# ABC_Maker_V1.net
KiCad netlist of a schematic drawn in Altium Designer
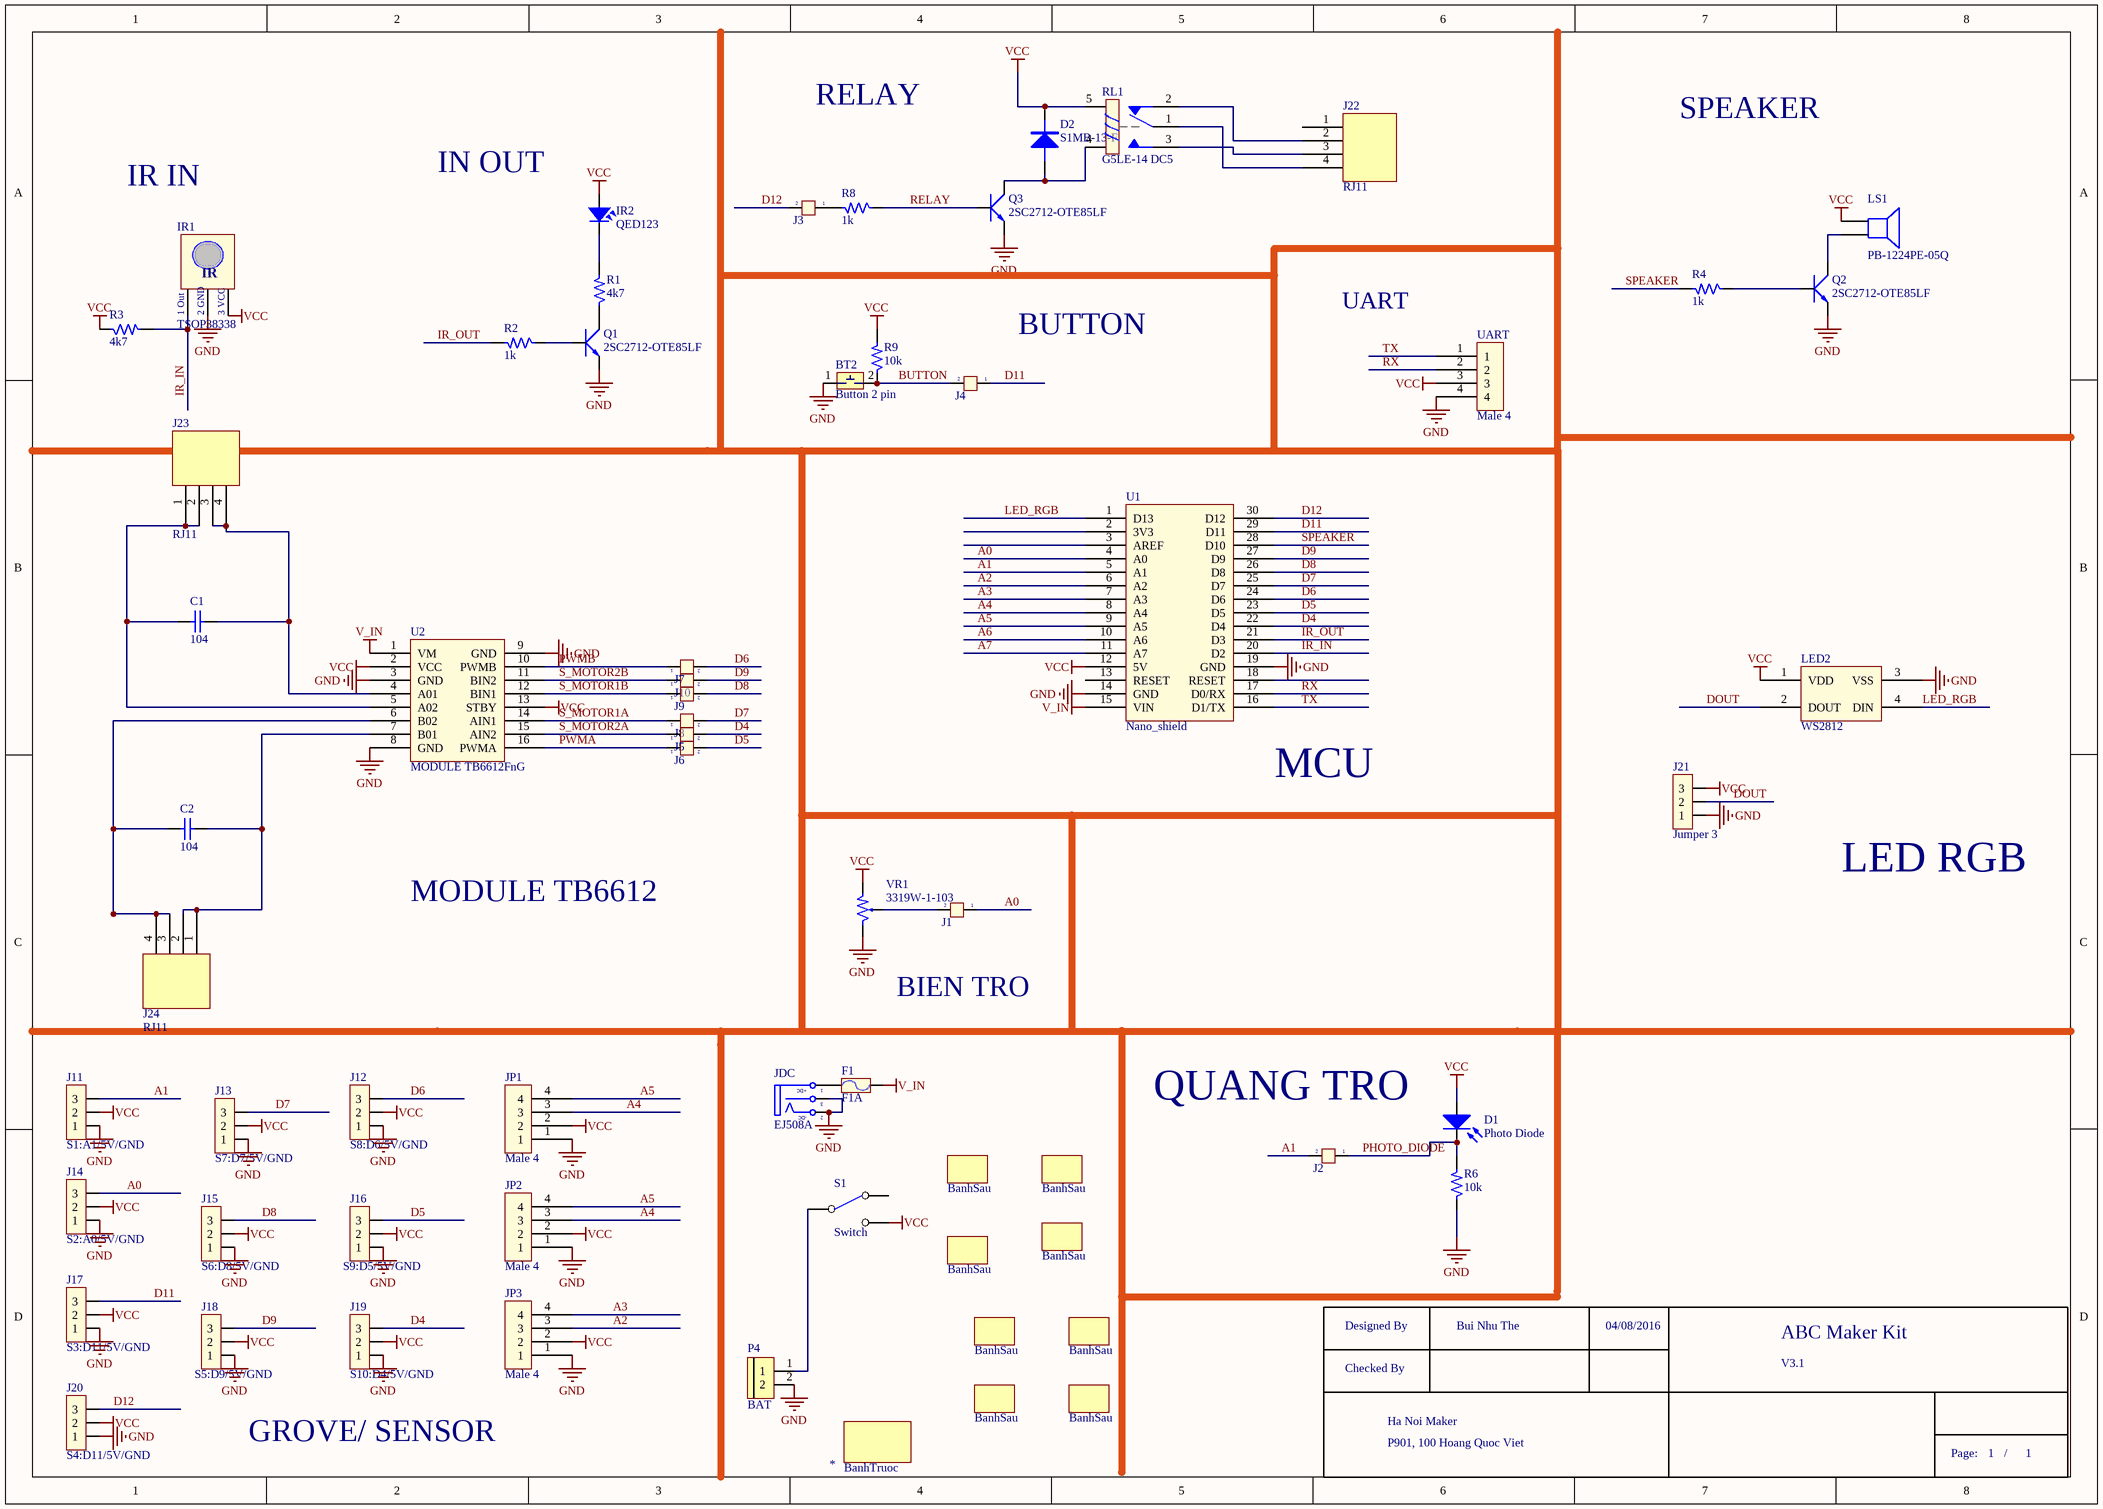
[diagram p0: ABC Maker V1.SchDoc]

(export (version "E")
  (design (tool "Eeschema 10.0.6"))
  (components
    (comp (ref "BT2") (value "Button 2 pin") (libsource (lib "switches") (part "Button 2 pin")))
    (comp (ref "C1") (value "104") (footprint "0805") (libsource (lib "BNTLIB") (part "Cap")))
    (comp (ref "C2") (value "104") (footprint "0805") (libsource (lib "BNTLIB") (part "Cap")))
    (comp (ref "D1")
      (value "Photo Diode")
      (footprint "LED-5 GRe")
      (description "Photosensitive Diode")
      (libsource (lib "BNTLIB") (part "Photo Diode"))
    )
    (comp (ref "D2")
      (value "S1MB-13-F")
      (description "Diode Standard 1000V (1kV) 1A Surface Mount SMB")
      (fields (field (name "MANUFACTURER") "Diodes Incorporated"))
      (libsource (lib "Diode") (part "S1MB-13-F"))
    )
    (comp (ref "F1")
      (value "F1A")
      (footprint "1206")
      (description "Fuse")
      (fields (field (name "DESIGNED BY") "VanDungEvn"))
      (libsource (lib "syhaunguyen") (part "Fuse"))
    )
    (comp (ref "IR1")
      (value "TSOP38338")
      (description "IC IR RCVR MOD 38KHZ DOME RADIAL")
      (fields (field (name "MANUFACTURER") "Vishay Semiconductor Opto Division"))
      (libsource (lib "Sensor") (part "TSOP38338"))
    )
    (comp (ref "IR2")
      (value "QED123")
      (description "Infrared Emitters 80mW/sr 1.7V IR LED")
      (fields (field (name "MANUFACTURER") "Fairchild Semiconductor"))
      (libsource (lib "Sensor") (part "QED123"))
    )
    (comp (ref "J1") (value "Jumper 2") (footprint "JP 2") (libsource (lib "BNTLIB") (part "JP 2")))
    (comp (ref "J2") (value "Jumper 2") (footprint "JP 2") (libsource (lib "BNTLIB") (part "JP 2")))
    (comp (ref "J3") (value "Jumper 2") (footprint "JP 2") (libsource (lib "BNTLIB") (part "JP 2")))
    (comp (ref "J4") (value "Jumper 2") (footprint "JP 2") (libsource (lib "BNTLIB") (part "JP 2")))
    (comp (ref "J5") (value "Jumper 2") (footprint "JP 2") (libsource (lib "") (part "JP 2_1")))
    (comp (ref "J6") (value "Jumper 2") (footprint "JP 2") (libsource (lib "") (part "JP 2_1")))
    (comp (ref "J7") (value "Jumper 2") (footprint "JP 2") (libsource (lib "") (part "JP 2_1")))
    (comp (ref "J8") (value "Jumper 2") (footprint "JP 2") (libsource (lib "") (part "JP 2_1")))
    (comp (ref "J9") (value "Jumper 2") (footprint "JP 2") (libsource (lib "") (part "JP 2_1")))
    (comp (ref "J10") (value "Jumper 2") (footprint "JP 2") (libsource (lib "") (part "JP 2_1")))
    (comp (ref "J11")
      (value "S1:A1/5V/GND")
      (footprint "JP 3")
      (description "Jumper 3")
      (libsource (lib "BNTLIB") (part "JP3_1"))
    )
    (comp (ref "J12")
      (value "S8:D6/5V/GND")
      (footprint "JP 3")
      (description "Jumper 3")
      (libsource (lib "BNTLIB") (part "JP3_1"))
    )
    (comp (ref "J13")
      (value "S7:D7/5V/GND")
      (footprint "JP 3")
      (description "Jumper 3")
      (libsource (lib "BNTLIB") (part "JP3_1"))
    )
    (comp (ref "J14")
      (value "S2:A0/5V/GND")
      (footprint "JP 3")
      (description "Jumper 3")
      (libsource (lib "BNTLIB") (part "JP3_1"))
    )
    (comp (ref "J15")
      (value "S6:D8/5V/GND")
      (footprint "JP 3")
      (description "Jumper 3")
      (libsource (lib "BNTLIB") (part "JP3_1"))
    )
    (comp (ref "J16")
      (value "S9:D5/5V/GND")
      (footprint "JP 3")
      (description "Jumper 3")
      (libsource (lib "BNTLIB") (part "JP3_1"))
    )
    (comp (ref "J17")
      (value "S3:D11/5V/GND")
      (footprint "JP 3")
      (description "Jumper 3")
      (libsource (lib "BNTLIB") (part "JP3_1"))
    )
    (comp (ref "J18")
      (value "S5:D9/5V/GND")
      (footprint "JP 3")
      (description "Jumper 3")
      (libsource (lib "BNTLIB") (part "JP3_1"))
    )
    (comp (ref "J19")
      (value "S10:D4/5V/GND")
      (footprint "JP 3")
      (description "Jumper 3")
      (libsource (lib "BNTLIB") (part "JP3_1"))
    )
    (comp (ref "J20")
      (value "S4:D11/5V/GND")
      (footprint "JP 3")
      (description "Jumper 3")
      (libsource (lib "BNTLIB") (part "JP3_1"))
    )
    (comp (ref "J21") (value "Jumper 3") (footprint "JP 3") (libsource (lib "BNTLIB") (part "JP3_1")))
    (comp (ref "J22")
      (value "RJ11")
      (description "Jack Modular Connector 6p6c (RJ11, RJ12, RJ14, RJ25) 90° Angle (Right) Unshielded Cat5")
      (fields
        (field (name "MANUFACTURER") "Wurth Electronics Inc")
        (field (name "MANUFACTURER PART NUMBER") "615006138421")
      )
      (libsource (lib "Jack") (part "615006138421"))
    )
    (comp (ref "J23")
      (value "RJ11")
      (description "Jack Modular Connector 6p6c (RJ11, RJ12, RJ14, RJ25) 90° Angle (Right) Unshielded Cat5")
      (fields
        (field (name "MANUFACTURER") "Wurth Electronics Inc")
        (field (name "MANUFACTURER PART NUMBER") "615006138421")
      )
      (libsource (lib "") (part "615006138421_1"))
    )
    (comp (ref "J24")
      (value "RJ11")
      (description "Jack Modular Connector 6p6c (RJ11, RJ12, RJ14, RJ25) 90° Angle (Right) Unshielded Cat5")
      (fields
        (field (name "MANUFACTURER") "Wurth Electronics Inc")
        (field (name "MANUFACTURER PART NUMBER") "615006138421")
      )
      (libsource (lib "") (part "615006138421_2"))
    )
    (comp (ref "JDC")
      (value "EJ508A")
      (description "Power Barrel Connector Jack 2.10mm ID (0.083\"), 5.50mm OD (0.217\") Through Hole, Right Angle")
      (fields (field (name "MANUFACTURER") "MPD (Memory Protection Devices)"))
      (libsource (lib "Jack") (part "EJ508A"))
    )
    (comp (ref "JP1")
      (value "Male 4")
      (description "4 Positions Header, Unshrouded Connector 0.100\" (2.54mm) Through Hole Gold or Gold, GXT™")
      (fields
        (field (name "MANUFACTURER") "Amphenol FCI")
        (field (name "MANUFACTURER PART NUMBER") "68001-104HLF")
      )
      (libsource (lib "Connector") (part "68001-104HLF"))
    )
    (comp (ref "JP2")
      (value "Male 4")
      (description "4 Positions Header, Unshrouded Connector 0.100\" (2.54mm) Through Hole Gold or Gold, GXT™")
      (fields
        (field (name "MANUFACTURER") "Amphenol FCI")
        (field (name "MANUFACTURER PART NUMBER") "68001-104HLF")
      )
      (libsource (lib "Connector") (part "68001-104HLF"))
    )
    (comp (ref "JP3")
      (value "Male 4")
      (description "4 Positions Header, Unshrouded Connector 0.100\" (2.54mm) Through Hole Gold or Gold, GXT™")
      (fields
        (field (name "MANUFACTURER") "Amphenol FCI")
        (field (name "MANUFACTURER PART NUMBER") "68001-104HLF")
      )
      (libsource (lib "Connector") (part "68001-104HLF"))
    )
    (comp (ref "LED2")
      (value "WS2812")
      (description "LED RGB WS2812 OR SK6812 1=10")
      (fields
        (field (name "MANUFACTURER") "Adafruit Industries LLC")
        (field (name "MANUFACTURER PART NUMBER") "1655")
      )
      (libsource (lib "Led") (part "1655"))
    )
    (comp (ref "LS1")
      (value "PB-1224PE-05Q")
      (description "Peak-Peak Signal Buzzer Single Tone 2.4kHz Magnetic 4.5 ~ 5.5V 85dB @ 5V, 10cm")
      (fields (field (name "MANUFACTURER") "Mallory Sonalert Products Inc."))
      (libsource (lib "Speaker") (part "PB-1224PE-05Q"))
    )
    (comp (ref "P4")
      (value "BAT")
      (footprint "CON2")
      (description "Big Header 2")
      (libsource (lib "BNTLIB") (part "Header 2"))
    )
    (comp (ref "Q1")
      (value "2SC2712-OTE85LF")
      (description "TRANS NPN 50V 0.15A S-MINI")
      (fields (field (name "MANUFACTURER") "Toshiba Semiconductor and Storage"))
      (libsource (lib "Transistor") (part "2SC2712-OTE85LF"))
    )
    (comp (ref "Q2")
      (value "2SC2712-OTE85LF")
      (description "TRANS NPN 50V 0.15A S-MINI")
      (fields (field (name "MANUFACTURER") "Toshiba Semiconductor and Storage"))
      (libsource (lib "Transistor") (part "2SC2712-OTE85LF"))
    )
    (comp (ref "Q3")
      (value "2SC2712-OTE85LF")
      (description "TRANS NPN 50V 0.15A S-MINI")
      (fields (field (name "MANUFACTURER") "Toshiba Semiconductor and Storage"))
      (libsource (lib "Transistor") (part "2SC2712-OTE85LF"))
    )
    (comp (ref "R1")
      (value "4k7")
      (description "RES SMD 4k7 OHM 5% 1/8W 0805")
      (fields
        (field (name "MANUFACTURER") "Rohm Semiconductor")
        (field (name "MANUFACTURER PART NUMBER") "MCR10ERTJ472")
      )
      (libsource (lib "Res") (part "MCR10ERTJ472"))
    )
    (comp (ref "R2")
      (value "1k")
      (description "RES SMD 1K OHM 5% 1/8W 0805")
      (fields
        (field (name "MANUFACTURER") "Rohm Semiconductor")
        (field (name "MANUFACTURER PART NUMBER") "MCR10ERTJ102")
      )
      (libsource (lib "Res") (part "MCR10ERTJ102"))
    )
    (comp (ref "R3")
      (value "4k7")
      (description "RES SMD 4k7 OHM 5% 1/8W 0805")
      (fields
        (field (name "MANUFACTURER") "Rohm Semiconductor")
        (field (name "MANUFACTURER PART NUMBER") "MCR10ERTJ472")
      )
      (libsource (lib "Res") (part "MCR10ERTJ472"))
    )
    (comp (ref "R4")
      (value "1k")
      (description "RES SMD 1K OHM 5% 1/8W 0805")
      (fields
        (field (name "MANUFACTURER") "Rohm Semiconductor")
        (field (name "MANUFACTURER PART NUMBER") "MCR10ERTJ102")
      )
      (libsource (lib "Res") (part "MCR10ERTJ102"))
    )
    (comp (ref "R6")
      (value "10k")
      (description "RES SMD 10K OHM 5% 1/8W 0805")
      (fields
        (field (name "MANUFACTURER") "Rohm Semiconductor")
        (field (name "MANUFACTURER PART NUMBER") "MCR10ERTJ103")
        (field (name ".CREATOR") "*")
      )
      (libsource (lib "Res") (part "MCR10ERTJ103"))
    )
    (comp (ref "R8")
      (value "1k")
      (description "RES SMD 1K OHM 5% 1/8W 0805")
      (fields
        (field (name "MANUFACTURER") "Rohm Semiconductor")
        (field (name "MANUFACTURER PART NUMBER") "MCR10ERTJ102")
      )
      (libsource (lib "Res") (part "MCR10ERTJ102"))
    )
    (comp (ref "R9")
      (value "10k")
      (description "RES SMD 10K OHM 5% 1/8W 0805")
      (fields
        (field (name "MANUFACTURER") "Rohm Semiconductor")
        (field (name "MANUFACTURER PART NUMBER") "MCR10ERTJ103")
        (field (name ".CREATOR") "*")
      )
      (libsource (lib "Res") (part "MCR10ERTJ103"))
    )
    (comp (ref "RL1")
      (value "G5LE-14 DC5")
      (description "General Purpose Relay SPDT (1 Form C) 5VDC Coil Through Hole")
      (fields (field (name "MANUFACTURER") "Omron Electronics Inc-EMC Div"))
      (libsource (lib "Relay") (part "G5LE-14 DC5"))
    )
    (comp (ref "S1") (value "Switch") (footprint "Switch") (libsource (lib "BNTLIB") (part "Switch")))
    (comp (ref "U1")
      (value "Nano_shield")
      (footprint "Nano_Shield_Dip")
      (libsource (lib "BNTLIB") (part "Nano_shield"))
    )
    (comp (ref "U2")
      (value "MODULE TB6612FnG")
      (footprint "TB6612FNG_DIP")
      (libsource (lib "BNTLIB") (part "MODULE TB6612FnG"))
    )
    (comp (ref "UART")
      (value "Male 4")
      (description "4 Positions Header, Unshrouded Connector 0.100\" (2.54mm) Through Hole Gold or Gold, GXT™")
      (fields
        (field (name "MANUFACTURER") "Amphenol FCI")
        (field (name "MANUFACTURER PART NUMBER") "68001-104HLF")
      )
      (libsource (lib "") (part "68001-104HLF_1"))
    )
    (comp (ref "VR1")
      (value "3319W-1-103")
      (description "10k Ohm 0.2W, 1/5W PC Pins Through Hole Trimmer Potentiometer Carbon 1 Turn Side Adjustment")
      (fields (field (name "MANUFACTURER") "Bourns Inc.") (field (name "TOLERANCE") "±25%"))
      (libsource (lib "Res") (part "3319W-1-103"))
    )
  )
  (nets
    (net (code "1") (name "/A0") (class "Default")
      (node (ref "J1") (pin "1") (pinfunction "1_1") (pintype "passive"))
      (node (ref "J14") (pin "3") (pinfunction "3_3") (pintype "passive"))
      (node (ref "U1") (pin "4") (pinfunction "A0_4") (pintype "passive"))
    )
    (net (code "2") (name "/A1") (class "Default")
      (node (ref "J11") (pin "3") (pinfunction "3_3") (pintype "passive"))
      (node (ref "J2") (pin "2") (pinfunction "2_2") (pintype "passive"))
      (node (ref "U1") (pin "5") (pinfunction "A1_5") (pintype "passive"))
    )
    (net (code "3") (name "/A2") (class "Default")
      (node (ref "JP3") (pin "3") (pinfunction "3_3") (pintype "passive"))
      (node (ref "U1") (pin "6") (pinfunction "A2_6") (pintype "passive"))
    )
    (net (code "4") (name "/A3") (class "Default")
      (node (ref "JP3") (pin "4") (pinfunction "4_4") (pintype "passive"))
      (node (ref "U1") (pin "7") (pinfunction "A3_7") (pintype "passive"))
    )
    (net (code "5") (name "/A4") (class "Default")
      (node (ref "JP1") (pin "3") (pinfunction "3_3") (pintype "passive"))
      (node (ref "JP2") (pin "3") (pinfunction "3_3") (pintype "passive"))
      (node (ref "U1") (pin "8") (pinfunction "A4_8") (pintype "passive"))
    )
    (net (code "6") (name "/A5") (class "Default")
      (node (ref "JP1") (pin "4") (pinfunction "4_4") (pintype "passive"))
      (node (ref "JP2") (pin "4") (pinfunction "4_4") (pintype "passive"))
      (node (ref "U1") (pin "9") (pinfunction "A5_9") (pintype "passive"))
    )
    (net (code "7") (name "/A6") (class "Default")
      (node (ref "U1") (pin "10") (pinfunction "A6_10") (pintype "passive"))
    )
    (net (code "8") (name "/A7") (class "Default")
      (node (ref "U1") (pin "11") (pinfunction "A7_11") (pintype "passive"))
    )
    (net (code "9") (name "/BUTTON") (class "Default")
      (node (ref "BT2") (pin "2") (pinfunction "2_2") (pintype "passive"))
      (node (ref "J4") (pin "2") (pinfunction "2_2") (pintype "passive"))
      (node (ref "R9") (pin "1") (pinfunction "1_1") (pintype "passive"))
    )
    (net (code "10") (name "/D4") (class "Default")
      (node (ref "J19") (pin "3") (pinfunction "3_3") (pintype "passive"))
      (node (ref "J5") (pin "2") (pinfunction "2_2") (pintype "passive"))
      (node (ref "U1") (pin "22") (pinfunction "D4_22") (pintype "passive"))
    )
    (net (code "11") (name "/D5") (class "Default")
      (node (ref "J16") (pin "3") (pinfunction "3_3") (pintype "passive"))
      (node (ref "J6") (pin "2") (pinfunction "2_2") (pintype "passive"))
      (node (ref "U1") (pin "23") (pinfunction "D5_23") (pintype "passive"))
    )
    (net (code "12") (name "/D6") (class "Default")
      (node (ref "J12") (pin "3") (pinfunction "3_3") (pintype "passive"))
      (node (ref "J7") (pin "2") (pinfunction "2_2") (pintype "passive"))
      (node (ref "U1") (pin "24") (pinfunction "D6_24") (pintype "passive"))
    )
    (net (code "13") (name "/D7") (class "Default")
      (node (ref "J13") (pin "3") (pinfunction "3_3") (pintype "passive"))
      (node (ref "J8") (pin "2") (pinfunction "2_2") (pintype "passive"))
      (node (ref "U1") (pin "25") (pinfunction "D7_25") (pintype "passive"))
    )
    (net (code "14") (name "/D8") (class "Default")
      (node (ref "J15") (pin "3") (pinfunction "3_3") (pintype "passive"))
      (node (ref "J9") (pin "2") (pinfunction "2_2") (pintype "passive"))
      (node (ref "U1") (pin "26") (pinfunction "D8_26") (pintype "passive"))
    )
    (net (code "15") (name "/D9") (class "Default")
      (node (ref "J10") (pin "2") (pinfunction "2_2") (pintype "passive"))
      (node (ref "J18") (pin "3") (pinfunction "3_3") (pintype "passive"))
      (node (ref "U1") (pin "27") (pinfunction "D9_27") (pintype "passive"))
    )
    (net (code "16") (name "/D11") (class "Default")
      (node (ref "J17") (pin "3") (pinfunction "3_3") (pintype "passive"))
      (node (ref "J4") (pin "1") (pinfunction "1_1") (pintype "passive"))
      (node (ref "U1") (pin "29") (pinfunction "D11_29") (pintype "passive"))
    )
    (net (code "17") (name "/D12") (class "Default")
      (node (ref "J20") (pin "3") (pinfunction "3_3") (pintype "passive"))
      (node (ref "J3") (pin "2") (pinfunction "2_2") (pintype "passive"))
      (node (ref "U1") (pin "30") (pinfunction "D12_30") (pintype "passive"))
    )
    (net (code "18") (name "/DOUT") (class "Default")
      (node (ref "J21") (pin "2") (pinfunction "2_2") (pintype "passive"))
      (node (ref "LED2") (pin "2") (pinfunction "DOUT_2") (pintype "passive"))
    )
    (net (code "19") (name "/IR_IN") (class "Default")
      (node (ref "IR1") (pin "1") (pinfunction "Out_1") (pintype "passive"))
      (node (ref "R3") (pin "2") (pinfunction "2_2") (pintype "passive"))
      (node (ref "U1") (pin "20") (pinfunction "D2_20") (pintype "passive"))
    )
    (net (code "20") (name "/IR_OUT") (class "Default")
      (node (ref "R2") (pin "2") (pinfunction "2_2") (pintype "passive"))
      (node (ref "U1") (pin "21") (pinfunction "D3_21") (pintype "passive"))
    )
    (net (code "21") (name "/LED_RGB") (class "Default")
      (node (ref "LED2") (pin "4") (pinfunction "DIN_4") (pintype "passive"))
      (node (ref "U1") (pin "1") (pinfunction "D13_1") (pintype "passive"))
    )
    (net (code "22") (name "/PHOTO_DIODE") (class "Default")
      (node (ref "D1") (pin "2") (pinfunction "K_2") (pintype "passive"))
      (node (ref "J2") (pin "1") (pinfunction "1_1") (pintype "passive"))
      (node (ref "R6") (pin "2") (pinfunction "2_2") (pintype "passive"))
    )
    (net (code "23") (name "/PWMA") (class "Default")
      (node (ref "J6") (pin "1") (pinfunction "1_1") (pintype "passive"))
      (node (ref "U2") (pin "16") (pinfunction "PWMA_16") (pintype "passive"))
    )
    (net (code "24") (name "/PWMB") (class "Default")
      (node (ref "J7") (pin "1") (pinfunction "1_1") (pintype "passive"))
      (node (ref "U2") (pin "10") (pinfunction "PWMB_10") (pintype "passive"))
    )
    (net (code "25") (name "/RELAY") (class "Default")
      (node (ref "Q3") (pin "3") (pinfunction "B_3") (pintype "passive"))
      (node (ref "R8") (pin "1") (pinfunction "1_1") (pintype "passive"))
    )
    (net (code "26") (name "/RX") (class "Default")
      (node (ref "U1") (pin "17") (pinfunction "D0/RX_17") (pintype "passive"))
      (node (ref "UART") (pin "2") (pinfunction "2_2") (pintype "passive"))
    )
    (net (code "27") (name "/SPEAKER") (class "Default")
      (node (ref "R4") (pin "2") (pinfunction "2_2") (pintype "passive"))
      (node (ref "U1") (pin "28") (pinfunction "D10_28") (pintype "passive"))
    )
    (net (code "28") (name "/S_MOTOR1A") (class "Default")
      (node (ref "J8") (pin "1") (pinfunction "1_1") (pintype "passive"))
      (node (ref "U2") (pin "14") (pinfunction "AIN1_14") (pintype "passive"))
    )
    (net (code "29") (name "/S_MOTOR1B") (class "Default")
      (node (ref "J9") (pin "1") (pinfunction "1_1") (pintype "passive"))
      (node (ref "U2") (pin "12") (pinfunction "BIN1_12") (pintype "passive"))
    )
    (net (code "30") (name "/S_MOTOR2A") (class "Default")
      (node (ref "J5") (pin "1") (pinfunction "1_1") (pintype "passive"))
      (node (ref "U2") (pin "15") (pinfunction "AIN2_15") (pintype "passive"))
    )
    (net (code "31") (name "/S_MOTOR2B") (class "Default")
      (node (ref "J10") (pin "1") (pinfunction "1_1") (pintype "passive"))
      (node (ref "U2") (pin "11") (pinfunction "BIN2_11") (pintype "passive"))
    )
    (net (code "32") (name "/TX") (class "Default")
      (node (ref "U1") (pin "16") (pinfunction "D1/TX_16") (pintype "passive"))
      (node (ref "UART") (pin "1") (pinfunction "1_1") (pintype "passive"))
    )
    (net (code "33") (name "GND") (class "Default")
      (node (ref "BT2") (pin "1") (pinfunction "1_1") (pintype "passive"))
      (node (ref "IR1") (pin "2") (pinfunction "GND_2") (pintype "passive"))
      (node (ref "J11") (pin "1") (pinfunction "1_1") (pintype "passive"))
      (node (ref "J12") (pin "1") (pinfunction "1_1") (pintype "passive"))
      (node (ref "J13") (pin "1") (pinfunction "1_1") (pintype "passive"))
      (node (ref "J14") (pin "1") (pinfunction "1_1") (pintype "passive"))
      (node (ref "J15") (pin "1") (pinfunction "1_1") (pintype "passive"))
      (node (ref "J16") (pin "1") (pinfunction "1_1") (pintype "passive"))
      (node (ref "J17") (pin "1") (pinfunction "1_1") (pintype "passive"))
      (node (ref "J18") (pin "1") (pinfunction "1_1") (pintype "passive"))
      (node (ref "J19") (pin "1") (pinfunction "1_1") (pintype "passive"))
      (node (ref "J20") (pin "1") (pinfunction "1_1") (pintype "passive"))
      (node (ref "J21") (pin "1") (pinfunction "1_1") (pintype "passive"))
      (node (ref "JDC") (pin "2") (pinfunction "TN_2") (pintype "passive"))
      (node (ref "JDC") (pin "3") (pinfunction "S_3") (pintype "power_in"))
      (node (ref "JP1") (pin "1") (pinfunction "1_1") (pintype "passive"))
      (node (ref "JP2") (pin "1") (pinfunction "1_1") (pintype "passive"))
      (node (ref "JP3") (pin "1") (pinfunction "1_1") (pintype "passive"))
      (node (ref "LED2") (pin "3") (pinfunction "VSS_3") (pintype "passive"))
      (node (ref "P4") (pin "2") (pinfunction "2_2") (pintype "passive"))
      (node (ref "Q1") (pin "1") (pinfunction "E_1") (pintype "passive"))
      (node (ref "Q2") (pin "1") (pinfunction "E_1") (pintype "passive"))
      (node (ref "Q3") (pin "1") (pinfunction "E_1") (pintype "passive"))
      (node (ref "R6") (pin "1") (pinfunction "1_1") (pintype "passive"))
      (node (ref "U1") (pin "14") (pinfunction "GND_14") (pintype "passive"))
      (node (ref "U1") (pin "19") (pinfunction "GND_19") (pintype "passive"))
      (node (ref "U2") (pin "3") (pinfunction "GND_3") (pintype "passive"))
      (node (ref "U2") (pin "8") (pinfunction "GND_8") (pintype "passive"))
      (node (ref "U2") (pin "9") (pinfunction "GND_9") (pintype "passive"))
      (node (ref "UART") (pin "4") (pinfunction "4_4") (pintype "passive"))
      (node (ref "VR1") (pin "3") (pinfunction "3_3") (pintype "passive"))
    )
    (net (code "34") (name "Net-(IR2-Pad2)") (class "Default")
      (node (ref "IR2") (pin "2") (pinfunction "2_2") (pintype "passive"))
      (node (ref "R1") (pin "2") (pinfunction "2_2") (pintype "passive"))
    )
    (net (code "35") (name "Net-(J1-Pad2)") (class "Default")
      (node (ref "J1") (pin "2") (pinfunction "2_2") (pintype "passive"))
      (node (ref "VR1") (pin "2") (pinfunction "2_2") (pintype "passive"))
    )
    (net (code "36") (name "Net-(J3-Pad1)") (class "Default")
      (node (ref "J3") (pin "1") (pinfunction "1_1") (pintype "passive"))
      (node (ref "R8") (pin "2") (pinfunction "2_2") (pintype "passive"))
    )
    (net (code "37") (name "Net-(J22-Pad2)") (class "Default")
      (node (ref "J22") (pin "2") (pintype "passive"))
      (node (ref "RL1") (pin "2") (pinfunction "2_2") (pintype "passive"))
    )
    (net (code "38") (name "Net-(J22-Pad3)") (class "Default")
      (node (ref "J22") (pin "3") (pintype "passive"))
      (node (ref "RL1") (pin "3") (pinfunction "3_3") (pintype "passive"))
    )
    (net (code "39") (name "Net-(J22-Pad4)") (class "Default")
      (node (ref "J22") (pin "4") (pintype "passive"))
      (node (ref "RL1") (pin "1") (pinfunction "1_1") (pintype "passive"))
    )
    (net (code "40") (name "Net-(JDC-T)") (class "Default")
      (node (ref "F1") (pin "1") (pinfunction "1_1") (pintype "passive"))
      (node (ref "JDC") (pin "1") (pinfunction "T_1") (pintype "passive"))
    )
    (net (code "41") (name "Net-(Q1-B)") (class "Default")
      (node (ref "Q1") (pin "3") (pinfunction "B_3") (pintype "passive"))
      (node (ref "R2") (pin "1") (pinfunction "1_1") (pintype "passive"))
    )
    (net (code "42") (name "Net-(Q1-C)") (class "Default")
      (node (ref "Q1") (pin "2") (pinfunction "C_2") (pintype "passive"))
      (node (ref "R1") (pin "1") (pinfunction "1_1") (pintype "passive"))
    )
    (net (code "43") (name "Net-(Q2-B)") (class "Default")
      (node (ref "Q2") (pin "3") (pinfunction "B_3") (pintype "passive"))
      (node (ref "R4") (pin "1") (pinfunction "1_1") (pintype "passive"))
    )
    (net (code "44") (name "Net-(Q2-C)") (class "Default")
      (node (ref "LS1") (pin "2") (pinfunction "2_2") (pintype "passive"))
      (node (ref "Q2") (pin "2") (pinfunction "C_2") (pintype "passive"))
    )
    (net (code "45") (name "Net-(Q3-C)") (class "Default")
      (node (ref "D2") (pin "1") (pinfunction "1_1") (pintype "passive"))
      (node (ref "Q3") (pin "2") (pinfunction "C_2") (pintype "passive"))
      (node (ref "RL1") (pin "4") (pinfunction "4_4") (pintype "passive"))
    )
    (net (code "46") (name "Net-(S1-COMMON)") (class "Default")
      (node (ref "P4") (pin "1") (pinfunction "1_1") (pintype "passive"))
      (node (ref "S1") (pin "2") (pinfunction "COMMON_2") (pintype "passive"))
    )
    (net (code "47") (name "Net-(U2-A01)") (class "Default")
      (node (ref "C1") (pin "1") (pinfunction "1_1") (pintype "passive"))
      (node (ref "J23") (pin "3") (pintype "passive"))
      (node (ref "J23") (pin "4") (pintype "passive"))
      (node (ref "U2") (pin "4") (pinfunction "A01_4") (pintype "passive"))
    )
    (net (code "48") (name "Net-(U2-A02)") (class "Default")
      (node (ref "C1") (pin "2") (pinfunction "2_2") (pintype "passive"))
      (node (ref "J23") (pin "1") (pintype "passive"))
      (node (ref "J23") (pin "2") (pintype "passive"))
      (node (ref "U2") (pin "5") (pinfunction "A02_5") (pintype "passive"))
    )
    (net (code "49") (name "Net-(U2-B01)") (class "Default")
      (node (ref "C2") (pin "1") (pinfunction "1_1") (pintype "passive"))
      (node (ref "J24") (pin "1") (pintype "passive"))
      (node (ref "J24") (pin "2") (pintype "passive"))
      (node (ref "U2") (pin "7") (pinfunction "B01_7") (pintype "passive"))
    )
    (net (code "50") (name "Net-(U2-B02)") (class "Default")
      (node (ref "C2") (pin "2") (pinfunction "2_2") (pintype "passive"))
      (node (ref "J24") (pin "3") (pintype "passive"))
      (node (ref "J24") (pin "4") (pintype "passive"))
      (node (ref "U2") (pin "6") (pinfunction "B02_6") (pintype "passive"))
    )
    (net (code "51") (name "VCC") (class "Default")
      (node (ref "D1") (pin "1") (pinfunction "A_1") (pintype "passive"))
      (node (ref "D2") (pin "2") (pinfunction "2_2") (pintype "passive"))
      (node (ref "IR1") (pin "3") (pinfunction "VCC_3") (pintype "passive"))
      (node (ref "IR2") (pin "1") (pinfunction "1_1") (pintype "passive"))
      (node (ref "J11") (pin "2") (pinfunction "2_2") (pintype "passive"))
      (node (ref "J12") (pin "2") (pinfunction "2_2") (pintype "passive"))
      (node (ref "J13") (pin "2") (pinfunction "2_2") (pintype "passive"))
      (node (ref "J14") (pin "2") (pinfunction "2_2") (pintype "passive"))
      (node (ref "J15") (pin "2") (pinfunction "2_2") (pintype "passive"))
      (node (ref "J16") (pin "2") (pinfunction "2_2") (pintype "passive"))
      (node (ref "J17") (pin "2") (pinfunction "2_2") (pintype "passive"))
      (node (ref "J18") (pin "2") (pinfunction "2_2") (pintype "passive"))
      (node (ref "J19") (pin "2") (pinfunction "2_2") (pintype "passive"))
      (node (ref "J20") (pin "2") (pinfunction "2_2") (pintype "passive"))
      (node (ref "J21") (pin "3") (pinfunction "3_3") (pintype "passive"))
      (node (ref "JP1") (pin "2") (pinfunction "2_2") (pintype "passive"))
      (node (ref "JP2") (pin "2") (pinfunction "2_2") (pintype "passive"))
      (node (ref "JP3") (pin "2") (pinfunction "2_2") (pintype "passive"))
      (node (ref "LED2") (pin "1") (pinfunction "VDD_1") (pintype "passive"))
      (node (ref "LS1") (pin "1") (pinfunction "1_1") (pintype "passive"))
      (node (ref "R3") (pin "1") (pinfunction "1_1") (pintype "passive"))
      (node (ref "R9") (pin "2") (pinfunction "2_2") (pintype "passive"))
      (node (ref "RL1") (pin "5") (pinfunction "5_5") (pintype "passive"))
      (node (ref "S1") (pin "3") (pinfunction "NO_3") (pintype "passive"))
      (node (ref "U1") (pin "12") (pinfunction "5V_12") (pintype "passive"))
      (node (ref "U2") (pin "13") (pinfunction "STBY_13") (pintype "passive"))
      (node (ref "U2") (pin "2") (pinfunction "VCC_2") (pintype "passive"))
      (node (ref "UART") (pin "3") (pinfunction "3_3") (pintype "passive"))
      (node (ref "VR1") (pin "1") (pinfunction "1_1") (pintype "passive"))
    )
    (net (code "52") (name "V_IN") (class "Default")
      (node (ref "F1") (pin "2") (pinfunction "2_2") (pintype "passive"))
      (node (ref "U1") (pin "15") (pinfunction "VIN_15") (pintype "passive"))
      (node (ref "U2") (pin "1") (pinfunction "VM_1") (pintype "passive"))
    )
    (net (code "53") (name "unconnected-(J22-Pad1)") (class "Default")
      (node (ref "J22") (pin "1") (pintype "passive"))
    )
    (net (code "54") (name "unconnected-(S1-NC-Pad1)") (class "Default")
      (node (ref "S1") (pin "1") (pinfunction "NC_1") (pintype "passive"))
    )
    (net (code "55") (name "unconnected-(U1-3V3-Pad2)") (class "Default")
      (node (ref "U1") (pin "2") (pinfunction "3V3_2") (pintype "passive"))
    )
    (net (code "56") (name "unconnected-(U1-AREF-Pad3)") (class "Default")
      (node (ref "U1") (pin "3") (pinfunction "AREF_3") (pintype "passive"))
    )
    (net (code "57") (name "unconnected-(U1-RESET-Pad13)") (class "Default")
      (node (ref "U1") (pin "13") (pinfunction "RESET_13") (pintype "passive"))
    )
    (net (code "58") (name "unconnected-(U1-RESET-Pad18)") (class "Default")
      (node (ref "U1") (pin "18") (pinfunction "RESET_18") (pintype "passive"))
    )
  )
)
